# BLDC_Driver_E3.net
KiCad netlist of a schematic drawn in Altium Designer
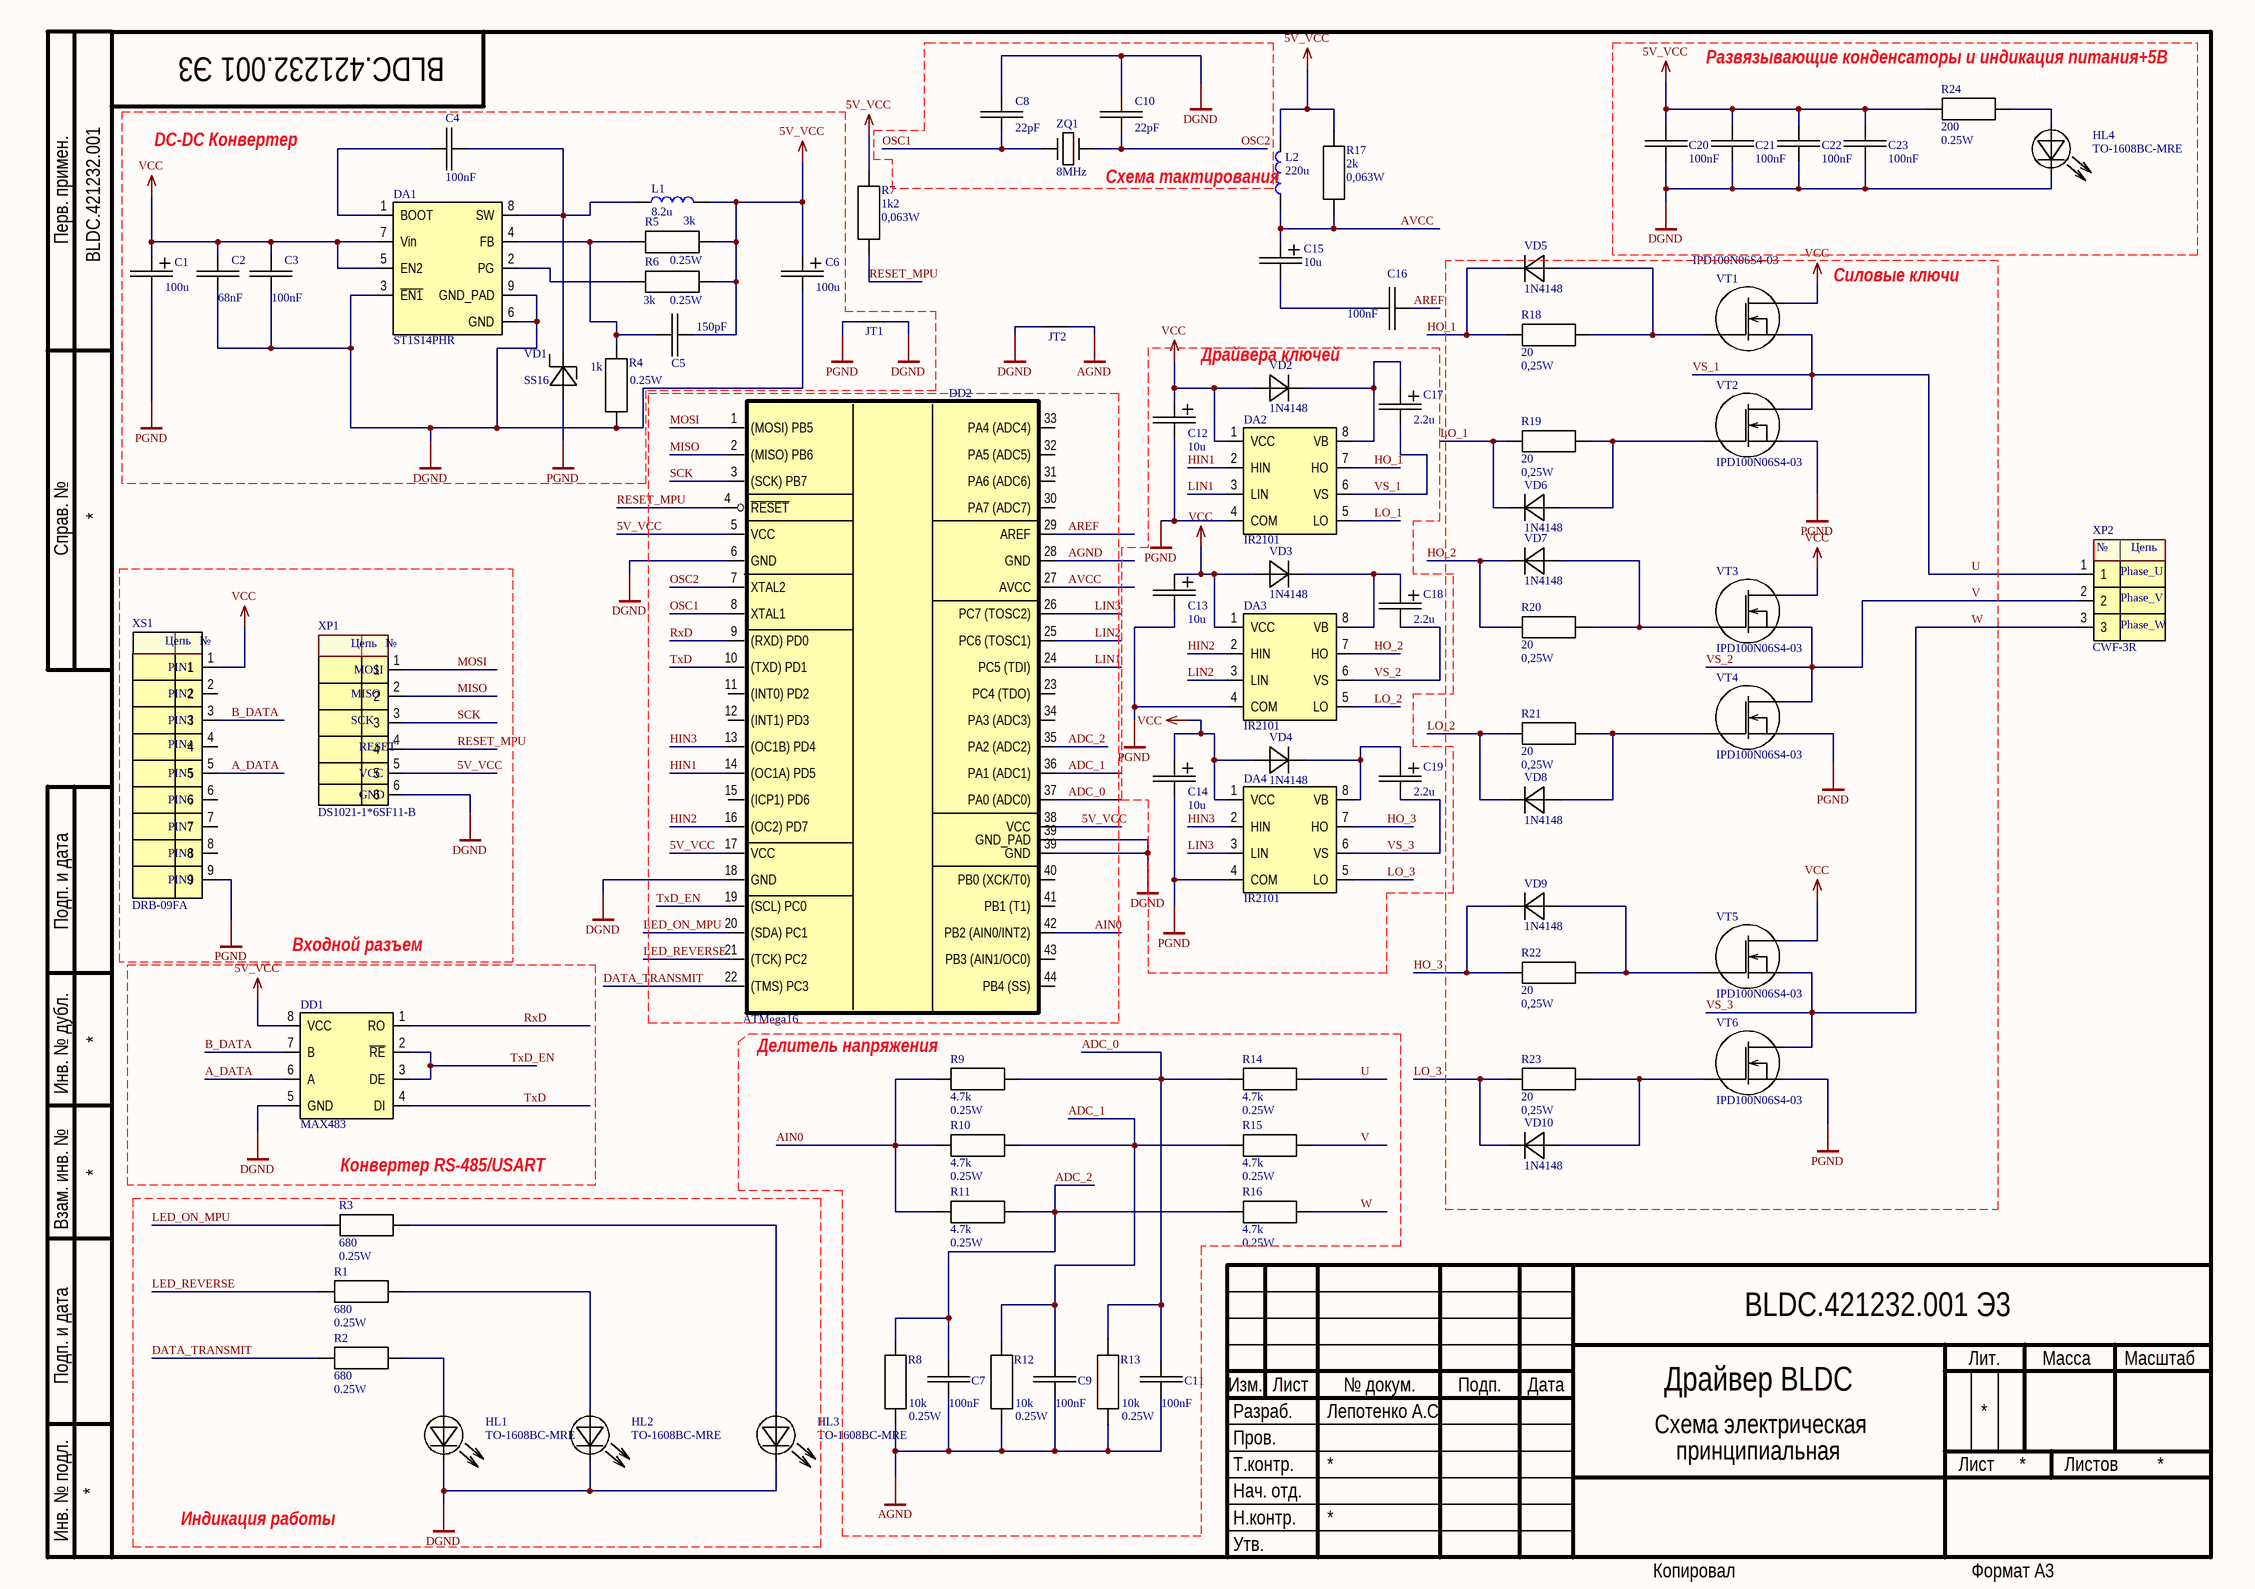
[diagram p0: BLDC_Driver_E3.SchDoc]

(export (version "E")
  (design (tool "Eeschema 10.0.6"))
  (components
    (comp (ref "C1")
      (value "100u")
      (footprint "ECAP_8x10")
      (fields
        (field (name "PART NUMBER") "B41121A6107M000")
        (field (name "MANUFACTURER") "Epcos")
        (field (name "POWER") "50V")
      )
      (libsource (lib "SchlibUGO") (part "Capasitor Electrolit"))
    )
    (comp (ref "C2")
      (value "68nF")
      (footprint "CAP1206")
      (fields
        (field (name "VOLTAGE") "100V")
        (field (name "PART NUMBER") "GRM31C5C1H683JA01L")
        (field (name "MANUFACTURER") "Murata")
      )
      (libsource (lib "SchlibUGO") (part "Capasitor"))
    )
    (comp (ref "C3")
      (value "100nF")
      (footprint "CAP1206")
      (fields
        (field (name "VOLTAGE") "100V")
        (field (name "PART NUMBER") "GRM31CR72A104KW03L")
        (field (name "MANUFACTURER") "Murata")
      )
      (libsource (lib "SchlibUGO") (part "Capasitor"))
    )
    (comp (ref "C4")
      (value "100nF")
      (footprint "CAP1206")
      (fields
        (field (name "VOLTAGE") "100V")
        (field (name "PART NUMBER") "GRM31CR72A104KW03L")
        (field (name "MANUFACTURER") "Murata")
      )
      (libsource (lib "SchlibUGO") (part "Capasitor"))
    )
    (comp (ref "C5")
      (value "150pF")
      (footprint "CAP0402_min")
      (fields
        (field (name "VOLTAGE") "50V")
        (field (name "PART NUMBER") "GRM1555C1H151JA01D")
        (field (name "MANUFACTURER") "Murata")
      )
      (libsource (lib "SchlibUGO") (part "Capasitor"))
    )
    (comp (ref "C6")
      (value "100u")
      (footprint "ECAP_8x10")
      (fields
        (field (name "PART NUMBER") "B41121A6107M000")
        (field (name "MANUFACTURER") "Epcos")
        (field (name "POWER") "50V")
      )
      (libsource (lib "SchlibUGO") (part "Capasitor Electrolit"))
    )
    (comp (ref "C7")
      (value "100nF")
      (footprint "CAP0402_min")
      (fields
        (field (name "VOLTAGE") "16V")
        (field (name "PART NUMBER") "GRM155R71C104KA88B")
        (field (name "MANUFACTURER") "Murata")
      )
      (libsource (lib "SchlibUGO") (part "Capasitor"))
    )
    (comp (ref "C8")
      (value "22pF")
      (footprint "CAP0402_min")
      (fields
        (field (name "VOLTAGE") "50V")
        (field (name "PART NUMBER") "CL05C220JB5NNNC")
        (field (name "MANUFACTURER") "Samsung")
      )
      (libsource (lib "SchlibUGO") (part "Capasitor"))
    )
    (comp (ref "C9")
      (value "100nF")
      (footprint "CAP0402_min")
      (fields
        (field (name "VOLTAGE") "16V")
        (field (name "PART NUMBER") "GRM155R71C104KA88B")
        (field (name "MANUFACTURER") "Murata")
      )
      (libsource (lib "SchlibUGO") (part "Capasitor"))
    )
    (comp (ref "C10")
      (value "22pF")
      (footprint "CAP0402_min")
      (fields
        (field (name "VOLTAGE") "50V")
        (field (name "PART NUMBER") "CL05C220JB5NNNC")
        (field (name "MANUFACTURER") "Samsung")
      )
      (libsource (lib "SchlibUGO") (part "Capasitor"))
    )
    (comp (ref "C11")
      (value "100nF")
      (footprint "CAP0402_min")
      (fields
        (field (name "VOLTAGE") "16V")
        (field (name "PART NUMBER") "GRM155R71C104KA88B")
        (field (name "MANUFACTURER") "Murata")
      )
      (libsource (lib "SchlibUGO") (part "Capasitor"))
    )
    (comp (ref "C12")
      (value "10u")
      (footprint "Type D")
      (fields
        (field (name "PART NUMBER") "TECAP10/25VD20")
        (field (name "MANUFACTURER") "Китай")
        (field (name "POWER") "25V")
      )
      (libsource (lib "SchlibUGO") (part "Capasitor Electrolit"))
    )
    (comp (ref "C13")
      (value "10u")
      (footprint "Type D")
      (fields
        (field (name "PART NUMBER") "TECAP10/25VD20")
        (field (name "MANUFACTURER") "Китай")
        (field (name "POWER") "25V")
      )
      (libsource (lib "SchlibUGO") (part "Capasitor Electrolit"))
    )
    (comp (ref "C14")
      (value "10u")
      (footprint "Type D")
      (fields
        (field (name "PART NUMBER") "TECAP10/25VD20")
        (field (name "MANUFACTURER") "Китай")
        (field (name "POWER") "25V")
      )
      (libsource (lib "SchlibUGO") (part "Capasitor Electrolit"))
    )
    (comp (ref "C15")
      (value "10u")
      (footprint "CAPTtantaltypeA")
      (fields
        (field (name "PART NUMBER") "TECAP10/10VA10")
        (field (name "MANUFACTURER") "Китай")
        (field (name "POWER") "10V")
      )
      (libsource (lib "SchlibUGO") (part "Capasitor Electrolit"))
    )
    (comp (ref "C16")
      (value "100nF")
      (footprint "CAP0402_min")
      (fields
        (field (name "VOLTAGE") "16V")
        (field (name "PART NUMBER") "GRM155R71C104KA88B")
        (field (name "MANUFACTURER") "Murata")
      )
      (libsource (lib "SchlibUGO") (part "Capasitor"))
    )
    (comp (ref "C17")
      (value "2.2u")
      (footprint "CAPASITOR TYPEB")
      (fields
        (field (name "PART NUMBER") "TECAP2.2/25VB20")
        (field (name "MANUFACTURER") "China")
        (field (name "POWER") "25V")
      )
      (libsource (lib "SchlibUGO") (part "Capasitor Electrolit"))
    )
    (comp (ref "C18")
      (value "2.2u")
      (footprint "CAPASITOR TYPEB")
      (fields
        (field (name "PART NUMBER") "TECAP2.2/25VB20")
        (field (name "MANUFACTURER") "China")
        (field (name "POWER") "25V")
      )
      (libsource (lib "SchlibUGO") (part "Capasitor Electrolit"))
    )
    (comp (ref "C19")
      (value "2.2u")
      (footprint "CAPASITOR TYPEB")
      (fields
        (field (name "PART NUMBER") "TECAP2.2/25VB20")
        (field (name "MANUFACTURER") "China")
        (field (name "POWER") "25V")
      )
      (libsource (lib "SchlibUGO") (part "Capasitor Electrolit"))
    )
    (comp (ref "C20")
      (value "100nF")
      (footprint "CAP0402_min")
      (fields
        (field (name "VOLTAGE") "16V")
        (field (name "PART NUMBER") "GRM155R71C104KA88B")
        (field (name "MANUFACTURER") "Murata")
      )
      (libsource (lib "SchlibUGO") (part "Capasitor"))
    )
    (comp (ref "C21")
      (value "100nF")
      (footprint "CAP0402_min")
      (fields
        (field (name "VOLTAGE") "16V")
        (field (name "PART NUMBER") "GRM155R71C104KA88B")
        (field (name "MANUFACTURER") "Murata")
      )
      (libsource (lib "SchlibUGO") (part "Capasitor"))
    )
    (comp (ref "C22")
      (value "100nF")
      (footprint "CAP0402_min")
      (fields
        (field (name "VOLTAGE") "16V")
        (field (name "PART NUMBER") "GRM155R71C104KA88B")
        (field (name "MANUFACTURER") "Murata")
      )
      (libsource (lib "SchlibUGO") (part "Capasitor"))
    )
    (comp (ref "C23")
      (value "100nF")
      (footprint "CAP0402_min")
      (fields
        (field (name "VOLTAGE") "16V")
        (field (name "PART NUMBER") "GRM155R71C104KA88B")
        (field (name "MANUFACTURER") "Murata")
      )
      (libsource (lib "SchlibUGO") (part "Capasitor"))
    )
    (comp (ref "DA1")
      (value "ST1S14PHR")
      (footprint "HSOP8_Termal")
      (fields (field (name "MANUFACTURER") "STM MicroElectronics"))
      (libsource (lib "SchlibUGO") (part "ST1S14PHR"))
    )
    (comp (ref "DA2")
      (value "IR2101")
      (footprint "SO-8")
      (fields (field (name "PART NUMBER") "IR2101SPBF"))
      (libsource (lib "SchlibUGO") (part "IR2101"))
    )
    (comp (ref "DA3")
      (value "IR2101")
      (footprint "SO-8")
      (fields (field (name "PART NUMBER") "IR2101SPBF"))
      (libsource (lib "SchlibUGO") (part "IR2101"))
    )
    (comp (ref "DA4")
      (value "IR2101")
      (footprint "SO-8")
      (fields (field (name "PART NUMBER") "IR2101SPBF"))
      (libsource (lib "SchlibUGO") (part "IR2101"))
    )
    (comp (ref "DD1") (value "MAX483") (footprint "SO-8") (libsource (lib "SchlibUGO") (part "MAX483")))
    (comp (ref "DD2")
      (value "ATMega16")
      (footprint "TQFP80P1200X1200X120-44N")
      (fields (field (name "MANUFACTURER") "ATmel") (field (name "PART NUMBER") "ATMega16"))
      (libsource (lib "Integrated_MicroprocessorLib") (part "ATMega 16"))
    )
    (comp (ref "HL1")
      (value "TO-1608BC-MRE")
      (footprint "LED1206")
      (fields (field (name "MANUFACTURER") "Taiwan Oasis Technology Co.,"))
      (libsource (lib "SchlibUGO") (part "LED"))
    )
    (comp (ref "HL2")
      (value "TO-1608BC-MRE")
      (footprint "LED1206")
      (fields (field (name "MANUFACTURER") "Taiwan Oasis Technology Co.,"))
      (libsource (lib "SchlibUGO") (part "LED"))
    )
    (comp (ref "HL3")
      (value "TO-1608BC-MRE")
      (footprint "LED1206")
      (fields (field (name "MANUFACTURER") "Taiwan Oasis Technology Co.,"))
      (libsource (lib "SchlibUGO") (part "LED"))
    )
    (comp (ref "HL4")
      (value "TO-1608BC-MRE")
      (footprint "LED1206")
      (fields (field (name "MANUFACTURER") "Taiwan Oasis Technology Co.,"))
      (libsource (lib "SchlibUGO") (part "LED"))
    )
    (comp (ref "JT1") (value "JT") (footprint "JT") (libsource (lib "SchlibUGO") (part "JT")))
    (comp (ref "JT2") (value "JT") (footprint "JT") (libsource (lib "SchlibUGO") (part "JT")))
    (comp (ref "L1")
      (value "8.2u")
      (footprint "LQH4N_1812")
      (fields (field (name "PART NUMBER") "LQH4N8R2K04") (field (name "MANUFACTURER") "Murata Manufacturing"))
      (libsource (lib "SchlibUGO") (part "Inductor"))
    )
    (comp (ref "L2")
      (value "220u")
      (footprint "453232")
      (fields (field (name "PART NUMBER") "CM453232-221KL") (field (name "MANUFACTURER") "Bourns"))
      (libsource (lib "SchlibUGO") (part "Inductor"))
    )
    (comp (ref "R1")
      (value "680")
      (footprint "1206")
      (fields
        (field (name "MANUFACTURER") "Тайвань")
        (field (name "PART NUMBER") "RC1206FR-07200RL")
        (field (name "POWER") "0.25W")
      )
      (libsource (lib "SchlibUGO") (part "Resistor"))
    )
    (comp (ref "R2")
      (value "680")
      (footprint "1206")
      (fields
        (field (name "MANUFACTURER") "Тайвань")
        (field (name "PART NUMBER") "RC1206FR-07200RL")
        (field (name "POWER") "0.25W")
      )
      (libsource (lib "SchlibUGO") (part "Resistor"))
    )
    (comp (ref "R3")
      (value "680")
      (footprint "1206")
      (fields
        (field (name "MANUFACTURER") "Тайвань")
        (field (name "PART NUMBER") "RC1206FR-07200RL")
        (field (name "POWER") "0.25W")
      )
      (libsource (lib "SchlibUGO") (part "Resistor"))
    )
    (comp (ref "R4")
      (value "1k")
      (footprint "1206")
      (fields
        (field (name "MANUFACTURER") "Taiwan Co")
        (field (name "PART NUMBER") "RC1206FR-071KL")
        (field (name "POWER") "0.25W")
      )
      (libsource (lib "SchlibUGO") (part "Resistor"))
    )
    (comp (ref "R5")
      (value "3k")
      (footprint "1206")
      (fields
        (field (name "MANUFACTURER") "Taiwan Co")
        (field (name "PART NUMBER") "RC1206FR-073KL")
        (field (name "POWER") "0.25W")
      )
      (libsource (lib "SchlibUGO") (part "Resistor"))
    )
    (comp (ref "R6")
      (value "3k")
      (footprint "1206")
      (fields
        (field (name "MANUFACTURER") "Taiwan Co")
        (field (name "PART NUMBER") "RC1206FR-073KL")
        (field (name "POWER") "0.25W")
      )
      (libsource (lib "SchlibUGO") (part "Resistor"))
    )
    (comp (ref "R7")
      (value "1k2")
      (footprint "0402")
      (fields
        (field (name "MANUFACTURER") "YAGEO")
        (field (name "PART NUMBER") "RC04021k2")
        (field (name "POWER") "0,063W")
      )
      (libsource (lib "SchlibUGO") (part "Resistor"))
    )
    (comp (ref "R8")
      (value "10k")
      (footprint "1206")
      (fields
        (field (name "MANUFACTURER") "Taiwan Co")
        (field (name "PART NUMBER") "RC1206JR-0710KL")
        (field (name "POWER") "0.25W")
      )
      (libsource (lib "SchlibUGO") (part "Resistor"))
    )
    (comp (ref "R9")
      (value "4.7k")
      (footprint "1206")
      (fields
        (field (name "MANUFACTURER") "Taiwan Co")
        (field (name "PART NUMBER") "RC1206FR-074K7L")
        (field (name "POWER") "0.25W")
      )
      (libsource (lib "SchlibUGO") (part "Resistor"))
    )
    (comp (ref "R10")
      (value "4.7k")
      (footprint "1206")
      (fields
        (field (name "MANUFACTURER") "Taiwan Co")
        (field (name "PART NUMBER") "RC1206FR-074K7L")
        (field (name "POWER") "0.25W")
      )
      (libsource (lib "SchlibUGO") (part "Resistor"))
    )
    (comp (ref "R11")
      (value "4.7k")
      (footprint "1206")
      (fields
        (field (name "MANUFACTURER") "Taiwan Co")
        (field (name "PART NUMBER") "RC1206FR-074K7L")
        (field (name "POWER") "0.25W")
      )
      (libsource (lib "SchlibUGO") (part "Resistor"))
    )
    (comp (ref "R12")
      (value "10k")
      (footprint "1206")
      (fields
        (field (name "MANUFACTURER") "Taiwan Co")
        (field (name "PART NUMBER") "RC1206JR-0710KL")
        (field (name "POWER") "0.25W")
      )
      (libsource (lib "SchlibUGO") (part "Resistor"))
    )
    (comp (ref "R13")
      (value "10k")
      (footprint "1206")
      (fields
        (field (name "MANUFACTURER") "Taiwan Co")
        (field (name "PART NUMBER") "RC1206JR-0710KL")
        (field (name "POWER") "0.25W")
      )
      (libsource (lib "SchlibUGO") (part "Resistor"))
    )
    (comp (ref "R14")
      (value "4.7k")
      (footprint "1206")
      (fields
        (field (name "MANUFACTURER") "Taiwan Co")
        (field (name "PART NUMBER") "RC1206FR-074K7L")
        (field (name "POWER") "0.25W")
      )
      (libsource (lib "SchlibUGO") (part "Resistor"))
    )
    (comp (ref "R15")
      (value "4.7k")
      (footprint "1206")
      (fields
        (field (name "MANUFACTURER") "Taiwan Co")
        (field (name "PART NUMBER") "RC1206FR-074K7L")
        (field (name "POWER") "0.25W")
      )
      (libsource (lib "SchlibUGO") (part "Resistor"))
    )
    (comp (ref "R16")
      (value "4.7k")
      (footprint "1206")
      (fields
        (field (name "MANUFACTURER") "Taiwan Co")
        (field (name "PART NUMBER") "RC1206FR-074K7L")
        (field (name "POWER") "0.25W")
      )
      (libsource (lib "SchlibUGO") (part "Resistor"))
    )
    (comp (ref "R17")
      (value "2k")
      (footprint "0402")
      (fields
        (field (name "MANUFACTURER") "Тайвань")
        (field (name "PART NUMBER") "RC0402FR-072KL")
        (field (name "POWER") "0,063W")
      )
      (libsource (lib "SchlibUGO") (part "Resistor"))
    )
    (comp (ref "R18")
      (value "20")
      (footprint "1206")
      (fields
        (field (name "MANUFACTURER") "Taivan CO")
        (field (name "PART NUMBER") "RC1206FR-0720RL")
        (field (name "POWER") "0,25W")
      )
      (libsource (lib "SchlibUGO") (part "Resistor"))
    )
    (comp (ref "R19")
      (value "20")
      (footprint "1206")
      (fields
        (field (name "MANUFACTURER") "Taivan CO")
        (field (name "PART NUMBER") "RC1206FR-0720RL")
        (field (name "POWER") "0,25W")
      )
      (libsource (lib "SchlibUGO") (part "Resistor"))
    )
    (comp (ref "R20")
      (value "20")
      (footprint "1206")
      (fields
        (field (name "MANUFACTURER") "Taivan CO")
        (field (name "PART NUMBER") "RC1206FR-0720RL")
        (field (name "POWER") "0,25W")
      )
      (libsource (lib "SchlibUGO") (part "Resistor"))
    )
    (comp (ref "R21")
      (value "20")
      (footprint "1206")
      (fields
        (field (name "MANUFACTURER") "Taivan CO")
        (field (name "PART NUMBER") "RC1206FR-0720RL")
        (field (name "POWER") "0,25W")
      )
      (libsource (lib "SchlibUGO") (part "Resistor"))
    )
    (comp (ref "R22")
      (value "20")
      (footprint "1206")
      (fields
        (field (name "MANUFACTURER") "Taivan CO")
        (field (name "PART NUMBER") "RC1206FR-0720RL")
        (field (name "POWER") "0,25W")
      )
      (libsource (lib "SchlibUGO") (part "Resistor"))
    )
    (comp (ref "R23")
      (value "20")
      (footprint "1206")
      (fields
        (field (name "MANUFACTURER") "Taivan CO")
        (field (name "PART NUMBER") "RC1206FR-0720RL")
        (field (name "POWER") "0,25W")
      )
      (libsource (lib "SchlibUGO") (part "Resistor"))
    )
    (comp (ref "R24")
      (value "200")
      (footprint "1206")
      (fields
        (field (name "MANUFACTURER") "Тайвань")
        (field (name "PART NUMBER") "RC1206FR-07680RL")
        (field (name "POWER") "0.25W")
      )
      (libsource (lib "SchlibUGO") (part "Resistor"))
    )
    (comp (ref "VD1")
      (value "SS16")
      (footprint "DO-214(SMA)")
      (fields (field (name "MANUFACTURER") "MIC"))
      (libsource (lib "Diode_Library") (part "Basic_Diode_shottki"))
    )
    (comp (ref "VD2")
      (value "1N4148")
      (footprint "SOD-23")
      (libsource (lib "Diode_Library") (part "Basic_Diode"))
    )
    (comp (ref "VD3")
      (value "1N4148")
      (footprint "SOD-23")
      (libsource (lib "Diode_Library") (part "Basic_Diode"))
    )
    (comp (ref "VD4")
      (value "1N4148")
      (footprint "SOD-23")
      (libsource (lib "Diode_Library") (part "Basic_Diode"))
    )
    (comp (ref "VD5")
      (value "1N4148")
      (footprint "SOD-23")
      (libsource (lib "Diode_Library") (part "Basic_Diode"))
    )
    (comp (ref "VD6")
      (value "1N4148")
      (footprint "SOD-23")
      (libsource (lib "Diode_Library") (part "Basic_Diode"))
    )
    (comp (ref "VD7")
      (value "1N4148")
      (footprint "SOD-23")
      (libsource (lib "Diode_Library") (part "Basic_Diode"))
    )
    (comp (ref "VD8")
      (value "1N4148")
      (footprint "SOD-23")
      (libsource (lib "Diode_Library") (part "Basic_Diode"))
    )
    (comp (ref "VD9")
      (value "1N4148")
      (footprint "SOD-23")
      (libsource (lib "Diode_Library") (part "Basic_Diode"))
    )
    (comp (ref "VD10")
      (value "1N4148")
      (footprint "SOD-23")
      (libsource (lib "Diode_Library") (part "Basic_Diode"))
    )
    (comp (ref "VT1")
      (value "IPD100N06S4-03")
      (footprint "D2PACK")
      (fields (field (name "MANUFACTURER") "Infinion"))
      (libsource (lib "Project_int_VT") (part "IPD100N06S4-03"))
    )
    (comp (ref "VT2")
      (value "IPD100N06S4-03")
      (footprint "D2PACK")
      (fields (field (name "MANUFACTURER") "Infinion"))
      (libsource (lib "Project_int_VT") (part "IPD100N06S4-03"))
    )
    (comp (ref "VT3")
      (value "IPD100N06S4-03")
      (footprint "D2PACK")
      (fields (field (name "MANUFACTURER") "Infinion"))
      (libsource (lib "Project_int_VT") (part "IPD100N06S4-03"))
    )
    (comp (ref "VT4")
      (value "IPD100N06S4-03")
      (footprint "D2PACK")
      (fields (field (name "MANUFACTURER") "Infinion"))
      (libsource (lib "Project_int_VT") (part "IPD100N06S4-03"))
    )
    (comp (ref "VT5")
      (value "IPD100N06S4-03")
      (footprint "D2PACK")
      (fields (field (name "MANUFACTURER") "Infinion"))
      (libsource (lib "Project_int_VT") (part "IPD100N06S4-03"))
    )
    (comp (ref "VT6")
      (value "IPD100N06S4-03")
      (footprint "D2PACK")
      (fields (field (name "MANUFACTURER") "Infinion"))
      (libsource (lib "Project_int_VT") (part "IPD100N06S4-03"))
    )
    (comp (ref "XP1")
      (value "DS1021-1*6SF11-B")
      (footprint "PLS6x1")
      (fields (field (name "MANUFACTURER") "ROhs"))
      (libsource (lib "SchlibUGO") (part "AVR Connector Programmer"))
    )
    (comp (ref "XP2")
      (value "CWF-3R")
      (footprint "CWF-3R")
      (fields (field (name "MANUFACTURER") "KLS"))
      (libsource (lib "SchlibUGO") (part "CWF-3R"))
    )
    (comp (ref "XS1")
      (value "DRB-09FA")
      (footprint "DRB-09FA")
      (fields (field (name "MANUFACTURER") "KLS"))
      (libsource (lib "SchlibUGO") (part "DRB-09FA"))
    )
    (comp (ref "ZQ1")
      (value "8MHz")
      (footprint "HC-49US")
      (fields (field (name "PART NUMBER") "8.000MHzHC-49US") (field (name "MANUFACTURER") "CHina"))
      (libsource (lib "SchlibUGO") (part "Rzanator"))
    )
  )
  (nets
    (net (code "1") (name "/ADC_0") (class "Default")
      (node (ref "C11") (pin "2") (pinfunction "2_2") (pintype "passive"))
      (node (ref "DD2") (pin "37") (pinfunction "PA0_(ADC0)_37") (pintype "passive"))
      (node (ref "R13") (pin "2") (pinfunction "2_2") (pintype "passive"))
      (node (ref "R14") (pin "1") (pinfunction "1_1") (pintype "passive"))
      (node (ref "R9") (pin "2") (pinfunction "2_2") (pintype "passive"))
    )
    (net (code "2") (name "/ADC_1") (class "Default")
      (node (ref "C9") (pin "2") (pinfunction "2_2") (pintype "passive"))
      (node (ref "DD2") (pin "36") (pinfunction "PA1_(ADC1)_36") (pintype "passive"))
      (node (ref "R10") (pin "2") (pinfunction "2_2") (pintype "passive"))
      (node (ref "R12") (pin "2") (pinfunction "2_2") (pintype "passive"))
      (node (ref "R15") (pin "1") (pinfunction "1_1") (pintype "passive"))
    )
    (net (code "3") (name "/ADC_2") (class "Default")
      (node (ref "C7") (pin "2") (pinfunction "2_2") (pintype "passive"))
      (node (ref "DD2") (pin "35") (pinfunction "PA2_(ADC2)_35") (pintype "passive"))
      (node (ref "R11") (pin "2") (pinfunction "2_2") (pintype "passive"))
      (node (ref "R16") (pin "1") (pinfunction "1_1") (pintype "passive"))
      (node (ref "R8") (pin "2") (pinfunction "2_2") (pintype "passive"))
    )
    (net (code "4") (name "/AIN0") (class "Default")
      (node (ref "DD2") (pin "42") (pinfunction "PB2_(AIN0/INT2)_42") (pintype "passive"))
      (node (ref "R10") (pin "1") (pinfunction "1_1") (pintype "passive"))
      (node (ref "R11") (pin "1") (pinfunction "1_1") (pintype "passive"))
      (node (ref "R9") (pin "1") (pinfunction "1_1") (pintype "passive"))
    )
    (net (code "5") (name "/AREF") (class "Default")
      (node (ref "C16") (pin "2") (pinfunction "2_2") (pintype "passive"))
      (node (ref "DD2") (pin "29") (pinfunction "AREF_29") (pintype "passive"))
    )
    (net (code "6") (name "/AVCC") (class "Default")
      (node (ref "C15") (pin "1") (pinfunction "1_1") (pintype "passive"))
      (node (ref "DD2") (pin "27") (pinfunction "AVCC_27") (pintype "passive"))
      (node (ref "L2") (pin "1") (pinfunction "1_1") (pintype "passive"))
      (node (ref "R17") (pin "1") (pinfunction "1_1") (pintype "passive"))
    )
    (net (code "7") (name "/A_DATA") (class "Default")
      (node (ref "DD1") (pin "6") (pinfunction "A_6") (pintype "passive"))
      (node (ref "XS1") (pin "5") (pinfunction "5_5") (pintype "passive"))
    )
    (net (code "8") (name "/B_DATA") (class "Default")
      (node (ref "DD1") (pin "7") (pinfunction "B_7") (pintype "passive"))
      (node (ref "XS1") (pin "3") (pinfunction "3_3") (pintype "passive"))
    )
    (net (code "9") (name "/DATA_TRANSMIT") (class "Default")
      (node (ref "DD2") (pin "22") (pinfunction "(TMS)_PC3_22") (pintype "passive"))
      (node (ref "R2") (pin "2") (pinfunction "2_2") (pintype "passive"))
    )
    (net (code "10") (name "/HIN1") (class "Default")
      (node (ref "DA2") (pin "2") (pinfunction "HIN_2") (pintype "passive"))
      (node (ref "DD2") (pin "14") (pinfunction "(OC1A)_PD5_14") (pintype "passive"))
    )
    (net (code "11") (name "/HIN2") (class "Default")
      (node (ref "DA3") (pin "2") (pinfunction "HIN_2") (pintype "passive"))
      (node (ref "DD2") (pin "16") (pinfunction "(OC2)_PD7_16") (pintype "passive"))
    )
    (net (code "12") (name "/HIN3") (class "Default")
      (node (ref "DA4") (pin "2") (pinfunction "HIN_2") (pintype "passive"))
      (node (ref "DD2") (pin "13") (pinfunction "(OC1B)_PD4_13") (pintype "passive"))
    )
    (net (code "13") (name "/HO_1") (class "Default")
      (node (ref "DA2") (pin "7") (pinfunction "HO_7") (pintype "passive"))
      (node (ref "R18") (pin "1") (pinfunction "1_1") (pintype "passive"))
      (node (ref "VD5") (pin "2") (pinfunction "2_2") (pintype "passive"))
    )
    (net (code "14") (name "/HO_2") (class "Default")
      (node (ref "DA3") (pin "7") (pinfunction "HO_7") (pintype "passive"))
      (node (ref "R20") (pin "1") (pinfunction "1_1") (pintype "passive"))
      (node (ref "VD7") (pin "2") (pinfunction "2_2") (pintype "passive"))
    )
    (net (code "15") (name "/HO_3") (class "Default")
      (node (ref "DA4") (pin "7") (pinfunction "HO_7") (pintype "passive"))
      (node (ref "R22") (pin "1") (pinfunction "1_1") (pintype "passive"))
      (node (ref "VD9") (pin "2") (pinfunction "2_2") (pintype "passive"))
    )
    (net (code "16") (name "/LED_ON_MPU") (class "Default")
      (node (ref "DD2") (pin "20") (pinfunction "(SDA)_PC1_20") (pintype "passive"))
      (node (ref "R3") (pin "2") (pinfunction "2_2") (pintype "passive"))
    )
    (net (code "17") (name "/LED_REVERSE") (class "Default")
      (node (ref "DD2") (pin "21") (pinfunction "(TCK)_PC2_21") (pintype "passive"))
      (node (ref "R1") (pin "2") (pinfunction "2_2") (pintype "passive"))
    )
    (net (code "18") (name "/LIN1") (class "Default")
      (node (ref "DA2") (pin "3") (pinfunction "LIN_3") (pintype "passive"))
      (node (ref "DD2") (pin "24") (pinfunction "PC5_(TDI)_24") (pintype "passive"))
    )
    (net (code "19") (name "/LIN2") (class "Default")
      (node (ref "DA3") (pin "3") (pinfunction "LIN_3") (pintype "passive"))
      (node (ref "DD2") (pin "25") (pinfunction "PC6_(TOSC1)_25") (pintype "passive"))
    )
    (net (code "20") (name "/LIN3") (class "Default")
      (node (ref "DA4") (pin "3") (pinfunction "LIN_3") (pintype "passive"))
      (node (ref "DD2") (pin "26") (pinfunction "PC7_(TOSC2)_26") (pintype "passive"))
    )
    (net (code "21") (name "/LO_1") (class "Default")
      (node (ref "DA2") (pin "5") (pinfunction "LO_5") (pintype "passive"))
      (node (ref "R19") (pin "1") (pinfunction "1_1") (pintype "passive"))
      (node (ref "VD6") (pin "2") (pinfunction "2_2") (pintype "passive"))
    )
    (net (code "22") (name "/LO_2") (class "Default")
      (node (ref "DA3") (pin "5") (pinfunction "LO_5") (pintype "passive"))
      (node (ref "R21") (pin "1") (pinfunction "1_1") (pintype "passive"))
      (node (ref "VD8") (pin "2") (pinfunction "2_2") (pintype "passive"))
    )
    (net (code "23") (name "/LO_3") (class "Default")
      (node (ref "DA4") (pin "5") (pinfunction "LO_5") (pintype "passive"))
      (node (ref "R23") (pin "1") (pinfunction "1_1") (pintype "passive"))
      (node (ref "VD10") (pin "2") (pinfunction "2_2") (pintype "passive"))
    )
    (net (code "24") (name "/MISO") (class "Default")
      (node (ref "DD2") (pin "2") (pinfunction "(MISO)_PB6_2") (pintype "passive"))
      (node (ref "XP1") (pin "2") (pinfunction "2_2") (pintype "passive"))
    )
    (net (code "25") (name "/MOSI") (class "Default")
      (node (ref "DD2") (pin "1") (pinfunction "(MOSI)_PB5_1") (pintype "passive"))
      (node (ref "XP1") (pin "1") (pinfunction "1_1") (pintype "passive"))
    )
    (net (code "26") (name "/OSC1") (class "Default")
      (node (ref "C8") (pin "2") (pinfunction "2_2") (pintype "passive"))
      (node (ref "DD2") (pin "8") (pinfunction "XTAL1_8") (pintype "passive"))
      (node (ref "ZQ1") (pin "1") (pinfunction "1_1") (pintype "passive"))
    )
    (net (code "27") (name "/OSC2") (class "Default")
      (node (ref "C10") (pin "2") (pinfunction "2_2") (pintype "passive"))
      (node (ref "DD2") (pin "7") (pinfunction "XTAL2_7") (pintype "passive"))
      (node (ref "ZQ1") (pin "3") (pinfunction "2_3") (pintype "passive"))
    )
    (net (code "28") (name "/RESET_MPU") (class "Default")
      (node (ref "DD2") (pin "4") (pinfunction "~{RESET}_4") (pintype "passive"))
      (node (ref "R7") (pin "1") (pinfunction "1_1") (pintype "passive"))
      (node (ref "XP1") (pin "4") (pinfunction "4_4") (pintype "passive"))
    )
    (net (code "29") (name "/RxD") (class "Default")
      (node (ref "DD1") (pin "1") (pinfunction "RO_1") (pintype "passive"))
      (node (ref "DD2") (pin "9") (pinfunction "(RXD)_PD0_9") (pintype "passive"))
    )
    (net (code "30") (name "/SCK") (class "Default")
      (node (ref "DD2") (pin "3") (pinfunction "(SCK)_PB7_3") (pintype "passive"))
      (node (ref "XP1") (pin "3") (pinfunction "3_3") (pintype "passive"))
    )
    (net (code "31") (name "/TxD") (class "Default")
      (node (ref "DD1") (pin "4") (pinfunction "DI_4") (pintype "passive"))
      (node (ref "DD2") (pin "10") (pinfunction "(TXD)_PD1_10") (pintype "passive"))
    )
    (net (code "32") (name "/TxD_EN") (class "Default")
      (node (ref "DD1") (pin "2") (pinfunction "~{RE}_2") (pintype "passive"))
      (node (ref "DD1") (pin "3") (pinfunction "DE_3") (pintype "passive"))
      (node (ref "DD2") (pin "19") (pinfunction "(SCL)_PC0_19") (pintype "passive"))
    )
    (net (code "33") (name "/U") (class "Default")
      (node (ref "C17") (pin "2") (pinfunction "2_2") (pintype "passive"))
      (node (ref "DA2") (pin "6") (pinfunction "VS_6") (pintype "passive"))
      (node (ref "R14") (pin "2") (pinfunction "2_2") (pintype "passive"))
      (node (ref "VT1") (pin "3") (pinfunction "Source_3") (pintype "passive"))
      (node (ref "VT2") (pin "2") (pinfunction "D_2") (pintype "passive"))
      (node (ref "XP2") (pin "1") (pinfunction "1_1") (pintype "passive"))
    )
    (net (code "34") (name "/V") (class "Default")
      (node (ref "C18") (pin "2") (pinfunction "2_2") (pintype "passive"))
      (node (ref "DA3") (pin "6") (pinfunction "VS_6") (pintype "passive"))
      (node (ref "R15") (pin "2") (pinfunction "2_2") (pintype "passive"))
      (node (ref "VT3") (pin "3") (pinfunction "Source_3") (pintype "passive"))
      (node (ref "VT4") (pin "2") (pinfunction "D_2") (pintype "passive"))
      (node (ref "XP2") (pin "2") (pinfunction "2_2") (pintype "passive"))
    )
    (net (code "35") (name "/VS_3") (class "Default")
      (node (ref "C19") (pin "2") (pinfunction "2_2") (pintype "passive"))
      (node (ref "DA4") (pin "6") (pinfunction "VS_6") (pintype "passive"))
      (node (ref "R16") (pin "2") (pinfunction "2_2") (pintype "passive"))
      (node (ref "VT5") (pin "3") (pinfunction "Source_3") (pintype "passive"))
      (node (ref "VT6") (pin "2") (pinfunction "D_2") (pintype "passive"))
      (node (ref "XP2") (pin "3") (pinfunction "3_3") (pintype "passive"))
    )
    (net (code "36") (name "5V_VCC") (class "Default")
      (node (ref "C20") (pin "2") (pinfunction "2_2") (pintype "passive"))
      (node (ref "C21") (pin "2") (pinfunction "2_2") (pintype "passive"))
      (node (ref "C22") (pin "2") (pinfunction "2_2") (pintype "passive"))
      (node (ref "C23") (pin "2") (pinfunction "2_2") (pintype "passive"))
      (node (ref "C5") (pin "2") (pinfunction "2_2") (pintype "passive"))
      (node (ref "C6") (pin "1") (pinfunction "1_1") (pintype "passive"))
      (node (ref "DD1") (pin "8") (pinfunction "VCC_8") (pintype "passive"))
      (node (ref "DD2") (pin "17") (pinfunction "VCC_17") (pintype "passive"))
      (node (ref "DD2") (pin "38") (pinfunction "VCC_38") (pintype "passive"))
      (node (ref "DD2") (pin "5") (pinfunction "VCC_5") (pintype "passive"))
      (node (ref "L1") (pin "2") (pinfunction "2_2") (pintype "passive"))
      (node (ref "L2") (pin "2") (pinfunction "2_2") (pintype "passive"))
      (node (ref "R17") (pin "2") (pinfunction "2_2") (pintype "passive"))
      (node (ref "R24") (pin "2") (pinfunction "2_2") (pintype "passive"))
      (node (ref "R5") (pin "2") (pinfunction "2_2") (pintype "passive"))
      (node (ref "R6") (pin "2") (pinfunction "2_2") (pintype "passive"))
      (node (ref "R7") (pin "2") (pinfunction "2_2") (pintype "passive"))
      (node (ref "XP1") (pin "5") (pinfunction "5_5") (pintype "passive"))
    )
    (net (code "37") (name "AGND") (class "Default")
      (node (ref "C11") (pin "1") (pinfunction "1_1") (pintype "passive"))
      (node (ref "C7") (pin "1") (pinfunction "1_1") (pintype "passive"))
      (node (ref "C9") (pin "1") (pinfunction "1_1") (pintype "passive"))
      (node (ref "DD2") (pin "28") (pinfunction "GND_28") (pintype "passive"))
      (node (ref "JT2") (pin "2") (pinfunction "2_2") (pintype "passive"))
      (node (ref "R12") (pin "1") (pinfunction "1_1") (pintype "passive"))
      (node (ref "R13") (pin "1") (pinfunction "1_1") (pintype "passive"))
      (node (ref "R8") (pin "1") (pinfunction "1_1") (pintype "passive"))
    )
    (net (code "38") (name "DGND") (class "Default")
      (node (ref "C10") (pin "1") (pinfunction "1_1") (pintype "passive"))
      (node (ref "C2") (pin "1") (pinfunction "1_1") (pintype "passive"))
      (node (ref "C20") (pin "1") (pinfunction "1_1") (pintype "passive"))
      (node (ref "C21") (pin "1") (pinfunction "1_1") (pintype "passive"))
      (node (ref "C22") (pin "1") (pinfunction "1_1") (pintype "passive"))
      (node (ref "C23") (pin "1") (pinfunction "1_1") (pintype "passive"))
      (node (ref "C3") (pin "1") (pinfunction "1_1") (pintype "passive"))
      (node (ref "C6") (pin "2") (pinfunction "2_2") (pintype "passive"))
      (node (ref "C8") (pin "1") (pinfunction "1_1") (pintype "passive"))
      (node (ref "DA1") (pin "3") (pinfunction "~{EN1}_3") (pintype "passive"))
      (node (ref "DA1") (pin "6") (pinfunction "GND_6") (pintype "passive"))
      (node (ref "DA1") (pin "9") (pinfunction "GND_PAD_9") (pintype "passive"))
      (node (ref "DD1") (pin "5") (pinfunction "GND_5") (pintype "passive"))
      (node (ref "DD2") (pin "18") (pinfunction "GND_18") (pintype "passive"))
      (node (ref "DD2") (pin "39") (pinfunction "GND_PAD_39") (pintype "passive"))
      (node (ref "DD2") (pin "6") (pinfunction "GND_6") (pintype "passive"))
      (node (ref "HL1") (pin "2") (pinfunction "2_2") (pintype "passive"))
      (node (ref "HL2") (pin "2") (pinfunction "2_2") (pintype "passive"))
      (node (ref "HL3") (pin "2") (pinfunction "2_2") (pintype "passive"))
      (node (ref "HL4") (pin "2") (pinfunction "2_2") (pintype "passive"))
      (node (ref "JT1") (pin "2") (pinfunction "2_2") (pintype "passive"))
      (node (ref "JT2") (pin "1") (pinfunction "1_1") (pintype "passive"))
      (node (ref "R4") (pin "1") (pinfunction "1_1") (pintype "passive"))
      (node (ref "XP1") (pin "6") (pinfunction "6_6") (pintype "passive"))
    )
    (net (code "39") (name "Net-(C15-Pad2)") (class "Default")
      (node (ref "C15") (pin "2") (pinfunction "2_2") (pintype "passive"))
      (node (ref "C16") (pin "1") (pinfunction "1_1") (pintype "passive"))
    )
    (net (code "40") (name "Net-(DA1-BOOT)") (class "Default")
      (node (ref "C4") (pin "2") (pinfunction "2_2") (pintype "passive"))
      (node (ref "DA1") (pin "1") (pinfunction "BOOT_1") (pintype "passive"))
    )
    (net (code "41") (name "Net-(DA1-FB)") (class "Default")
      (node (ref "C5") (pin "1") (pinfunction "1_1") (pintype "passive"))
      (node (ref "DA1") (pin "4") (pinfunction "FB_4") (pintype "passive"))
      (node (ref "R4") (pin "2") (pinfunction "2_2") (pintype "passive"))
      (node (ref "R5") (pin "1") (pinfunction "1_1") (pintype "passive"))
    )
    (net (code "42") (name "Net-(DA1-PG)") (class "Default")
      (node (ref "DA1") (pin "2") (pinfunction "PG_2") (pintype "passive"))
      (node (ref "R6") (pin "1") (pinfunction "1_1") (pintype "passive"))
    )
    (net (code "43") (name "Net-(DA1-SW)") (class "Default")
      (node (ref "C4") (pin "1") (pinfunction "1_1") (pintype "passive"))
      (node (ref "DA1") (pin "8") (pinfunction "SW_8") (pintype "passive"))
      (node (ref "L1") (pin "1") (pinfunction "1_1") (pintype "passive"))
      (node (ref "VD1") (pin "2") (pinfunction "2_2") (pintype "passive"))
    )
    (net (code "44") (name "Net-(DA2-VB)") (class "Default")
      (node (ref "C17") (pin "1") (pinfunction "1_1") (pintype "passive"))
      (node (ref "DA2") (pin "8") (pinfunction "VB_8") (pintype "passive"))
      (node (ref "VD2") (pin "2") (pinfunction "2_2") (pintype "passive"))
    )
    (net (code "45") (name "Net-(DA3-VB)") (class "Default")
      (node (ref "C18") (pin "1") (pinfunction "1_1") (pintype "passive"))
      (node (ref "DA3") (pin "8") (pinfunction "VB_8") (pintype "passive"))
      (node (ref "VD3") (pin "2") (pinfunction "2_2") (pintype "passive"))
    )
    (net (code "46") (name "Net-(DA4-VB)") (class "Default")
      (node (ref "C19") (pin "1") (pinfunction "1_1") (pintype "passive"))
      (node (ref "DA4") (pin "8") (pinfunction "VB_8") (pintype "passive"))
      (node (ref "VD4") (pin "2") (pinfunction "2_2") (pintype "passive"))
    )
    (net (code "47") (name "Net-(HL1-Pad1)") (class "Default")
      (node (ref "HL1") (pin "1") (pinfunction "1_1") (pintype "passive"))
      (node (ref "R2") (pin "1") (pinfunction "1_1") (pintype "passive"))
    )
    (net (code "48") (name "Net-(HL2-Pad1)") (class "Default")
      (node (ref "HL2") (pin "1") (pinfunction "1_1") (pintype "passive"))
      (node (ref "R1") (pin "1") (pinfunction "1_1") (pintype "passive"))
    )
    (net (code "49") (name "Net-(HL3-Pad1)") (class "Default")
      (node (ref "HL3") (pin "1") (pinfunction "1_1") (pintype "passive"))
      (node (ref "R3") (pin "1") (pinfunction "1_1") (pintype "passive"))
    )
    (net (code "50") (name "Net-(HL4-Pad1)") (class "Default")
      (node (ref "HL4") (pin "1") (pinfunction "1_1") (pintype "passive"))
      (node (ref "R24") (pin "1") (pinfunction "1_1") (pintype "passive"))
    )
    (net (code "51") (name "Net-(VT1-G)") (class "Default")
      (node (ref "R18") (pin "2") (pinfunction "2_2") (pintype "passive"))
      (node (ref "VD5") (pin "1") (pinfunction "1_1") (pintype "passive"))
      (node (ref "VT1") (pin "1") (pinfunction "G_1") (pintype "passive"))
    )
    (net (code "52") (name "Net-(VT2-G)") (class "Default")
      (node (ref "R19") (pin "2") (pinfunction "2_2") (pintype "passive"))
      (node (ref "VD6") (pin "1") (pinfunction "1_1") (pintype "passive"))
      (node (ref "VT2") (pin "1") (pinfunction "G_1") (pintype "passive"))
    )
    (net (code "53") (name "Net-(VT3-G)") (class "Default")
      (node (ref "R20") (pin "2") (pinfunction "2_2") (pintype "passive"))
      (node (ref "VD7") (pin "1") (pinfunction "1_1") (pintype "passive"))
      (node (ref "VT3") (pin "1") (pinfunction "G_1") (pintype "passive"))
    )
    (net (code "54") (name "Net-(VT4-G)") (class "Default")
      (node (ref "R21") (pin "2") (pinfunction "2_2") (pintype "passive"))
      (node (ref "VD8") (pin "1") (pinfunction "1_1") (pintype "passive"))
      (node (ref "VT4") (pin "1") (pinfunction "G_1") (pintype "passive"))
    )
    (net (code "55") (name "Net-(VT5-G)") (class "Default")
      (node (ref "R22") (pin "2") (pinfunction "2_2") (pintype "passive"))
      (node (ref "VD9") (pin "1") (pinfunction "1_1") (pintype "passive"))
      (node (ref "VT5") (pin "1") (pinfunction "G_1") (pintype "passive"))
    )
    (net (code "56") (name "Net-(VT6-G)") (class "Default")
      (node (ref "R23") (pin "2") (pinfunction "2_2") (pintype "passive"))
      (node (ref "VD10") (pin "1") (pinfunction "1_1") (pintype "passive"))
      (node (ref "VT6") (pin "1") (pinfunction "G_1") (pintype "passive"))
    )
    (net (code "57") (name "PGND") (class "Default")
      (node (ref "C1") (pin "2") (pinfunction "2_2") (pintype "passive"))
      (node (ref "C12") (pin "2") (pinfunction "2_2") (pintype "passive"))
      (node (ref "C13") (pin "2") (pinfunction "2_2") (pintype "passive"))
      (node (ref "C14") (pin "2") (pinfunction "2_2") (pintype "passive"))
      (node (ref "DA2") (pin "4") (pinfunction "COM_4") (pintype "passive"))
      (node (ref "DA3") (pin "4") (pinfunction "COM_4") (pintype "passive"))
      (node (ref "DA4") (pin "4") (pinfunction "COM_4") (pintype "passive"))
      (node (ref "JT1") (pin "1") (pinfunction "1_1") (pintype "passive"))
      (node (ref "VD1") (pin "1") (pinfunction "1_1") (pintype "passive"))
      (node (ref "VT2") (pin "3") (pinfunction "Source_3") (pintype "passive"))
      (node (ref "VT4") (pin "3") (pinfunction "Source_3") (pintype "passive"))
      (node (ref "VT6") (pin "3") (pinfunction "Source_3") (pintype "passive"))
      (node (ref "XS1") (pin "9") (pinfunction "9_9") (pintype "passive"))
    )
    (net (code "58") (name "VCC") (class "Default")
      (node (ref "C1") (pin "1") (pinfunction "1_1") (pintype "passive"))
      (node (ref "C12") (pin "1") (pinfunction "1_1") (pintype "passive"))
      (node (ref "C13") (pin "1") (pinfunction "1_1") (pintype "passive"))
      (node (ref "C14") (pin "1") (pinfunction "1_1") (pintype "passive"))
      (node (ref "C2") (pin "2") (pinfunction "2_2") (pintype "passive"))
      (node (ref "C3") (pin "2") (pinfunction "2_2") (pintype "passive"))
      (node (ref "DA1") (pin "5") (pinfunction "EN2_5") (pintype "passive"))
      (node (ref "DA1") (pin "7") (pinfunction "Vin_7") (pintype "passive"))
      (node (ref "DA2") (pin "1") (pinfunction "VCC_1") (pintype "passive"))
      (node (ref "DA3") (pin "1") (pinfunction "VCC_1") (pintype "passive"))
      (node (ref "DA4") (pin "1") (pinfunction "VCC_1") (pintype "passive"))
      (node (ref "VD2") (pin "1") (pinfunction "1_1") (pintype "passive"))
      (node (ref "VD3") (pin "1") (pinfunction "1_1") (pintype "passive"))
      (node (ref "VD4") (pin "1") (pinfunction "1_1") (pintype "passive"))
      (node (ref "VT1") (pin "2") (pinfunction "D_2") (pintype "passive"))
      (node (ref "VT3") (pin "2") (pinfunction "D_2") (pintype "passive"))
      (node (ref "VT5") (pin "2") (pinfunction "D_2") (pintype "passive"))
      (node (ref "XS1") (pin "1") (pinfunction "1_1") (pintype "passive"))
    )
    (net (code "59") (name "unconnected-(DD2-(ICP1)_PD6-Pad15)") (class "Default")
      (node (ref "DD2") (pin "15") (pinfunction "(ICP1)_PD6_15") (pintype "passive"))
    )
    (net (code "60") (name "unconnected-(DD2-(INT0)_PD2-Pad11)") (class "Default")
      (node (ref "DD2") (pin "11") (pinfunction "(INT0)_PD2_11") (pintype "passive"))
    )
    (net (code "61") (name "unconnected-(DD2-(INT1)_PD3-Pad12)") (class "Default")
      (node (ref "DD2") (pin "12") (pinfunction "(INT1)_PD3_12") (pintype "passive"))
    )
    (net (code "62") (name "unconnected-(DD2-PA3_(ADC3)-Pad34)") (class "Default")
      (node (ref "DD2") (pin "34") (pinfunction "PA3_(ADC3)_34") (pintype "passive"))
    )
    (net (code "63") (name "unconnected-(DD2-PA4_(ADC4)-Pad33)") (class "Default")
      (node (ref "DD2") (pin "33") (pinfunction "PA4_(ADC4)_33") (pintype "passive"))
    )
    (net (code "64") (name "unconnected-(DD2-PA5_(ADC5)-Pad32)") (class "Default")
      (node (ref "DD2") (pin "32") (pinfunction "PA5_(ADC5)_32") (pintype "passive"))
    )
    (net (code "65") (name "unconnected-(DD2-PA6_(ADC6)-Pad31)") (class "Default")
      (node (ref "DD2") (pin "31") (pinfunction "PA6_(ADC6)_31") (pintype "passive"))
    )
    (net (code "66") (name "unconnected-(DD2-PA7_(ADC7)-Pad30)") (class "Default")
      (node (ref "DD2") (pin "30") (pinfunction "PA7_(ADC7)_30") (pintype "passive"))
    )
    (net (code "67") (name "unconnected-(DD2-PB0_(XCK{slash}T0)-Pad40)") (class "Default")
      (node (ref "DD2") (pin "40") (pinfunction "PB0_(XCK/T0)_40") (pintype "passive"))
    )
    (net (code "68") (name "unconnected-(DD2-PB1_(T1)-Pad41)") (class "Default")
      (node (ref "DD2") (pin "41") (pinfunction "PB1_(T1)_41") (pintype "passive"))
    )
    (net (code "69") (name "unconnected-(DD2-PB3_(AIN1{slash}OC0)-Pad43)") (class "Default")
      (node (ref "DD2") (pin "43") (pinfunction "PB3_(AIN1/OC0)_43") (pintype "passive"))
    )
    (net (code "70") (name "unconnected-(DD2-PB4_(SS)-Pad44)") (class "Default")
      (node (ref "DD2") (pin "44") (pinfunction "PB4_(SS)_44") (pintype "passive"))
    )
    (net (code "71") (name "unconnected-(DD2-PC4_(TDO)-Pad23)") (class "Default")
      (node (ref "DD2") (pin "23") (pinfunction "PC4_(TDO)_23") (pintype "passive"))
    )
    (net (code "72") (name "unconnected-(XS1-Pad2)") (class "Default")
      (node (ref "XS1") (pin "2") (pinfunction "2_2") (pintype "passive"))
    )
    (net (code "73") (name "unconnected-(XS1-Pad4)") (class "Default")
      (node (ref "XS1") (pin "4") (pinfunction "4_4") (pintype "passive"))
    )
    (net (code "74") (name "unconnected-(XS1-Pad6)") (class "Default")
      (node (ref "XS1") (pin "6") (pinfunction "6_6") (pintype "passive"))
    )
    (net (code "75") (name "unconnected-(XS1-Pad7)") (class "Default")
      (node (ref "XS1") (pin "7") (pinfunction "7_7") (pintype "passive"))
    )
    (net (code "76") (name "unconnected-(XS1-Pad8)") (class "Default")
      (node (ref "XS1") (pin "8") (pinfunction "8_8") (pintype "passive"))
    )
  )
)
